# LaserSupply.net
KiCad netlist of a schematic drawn in EAGLE
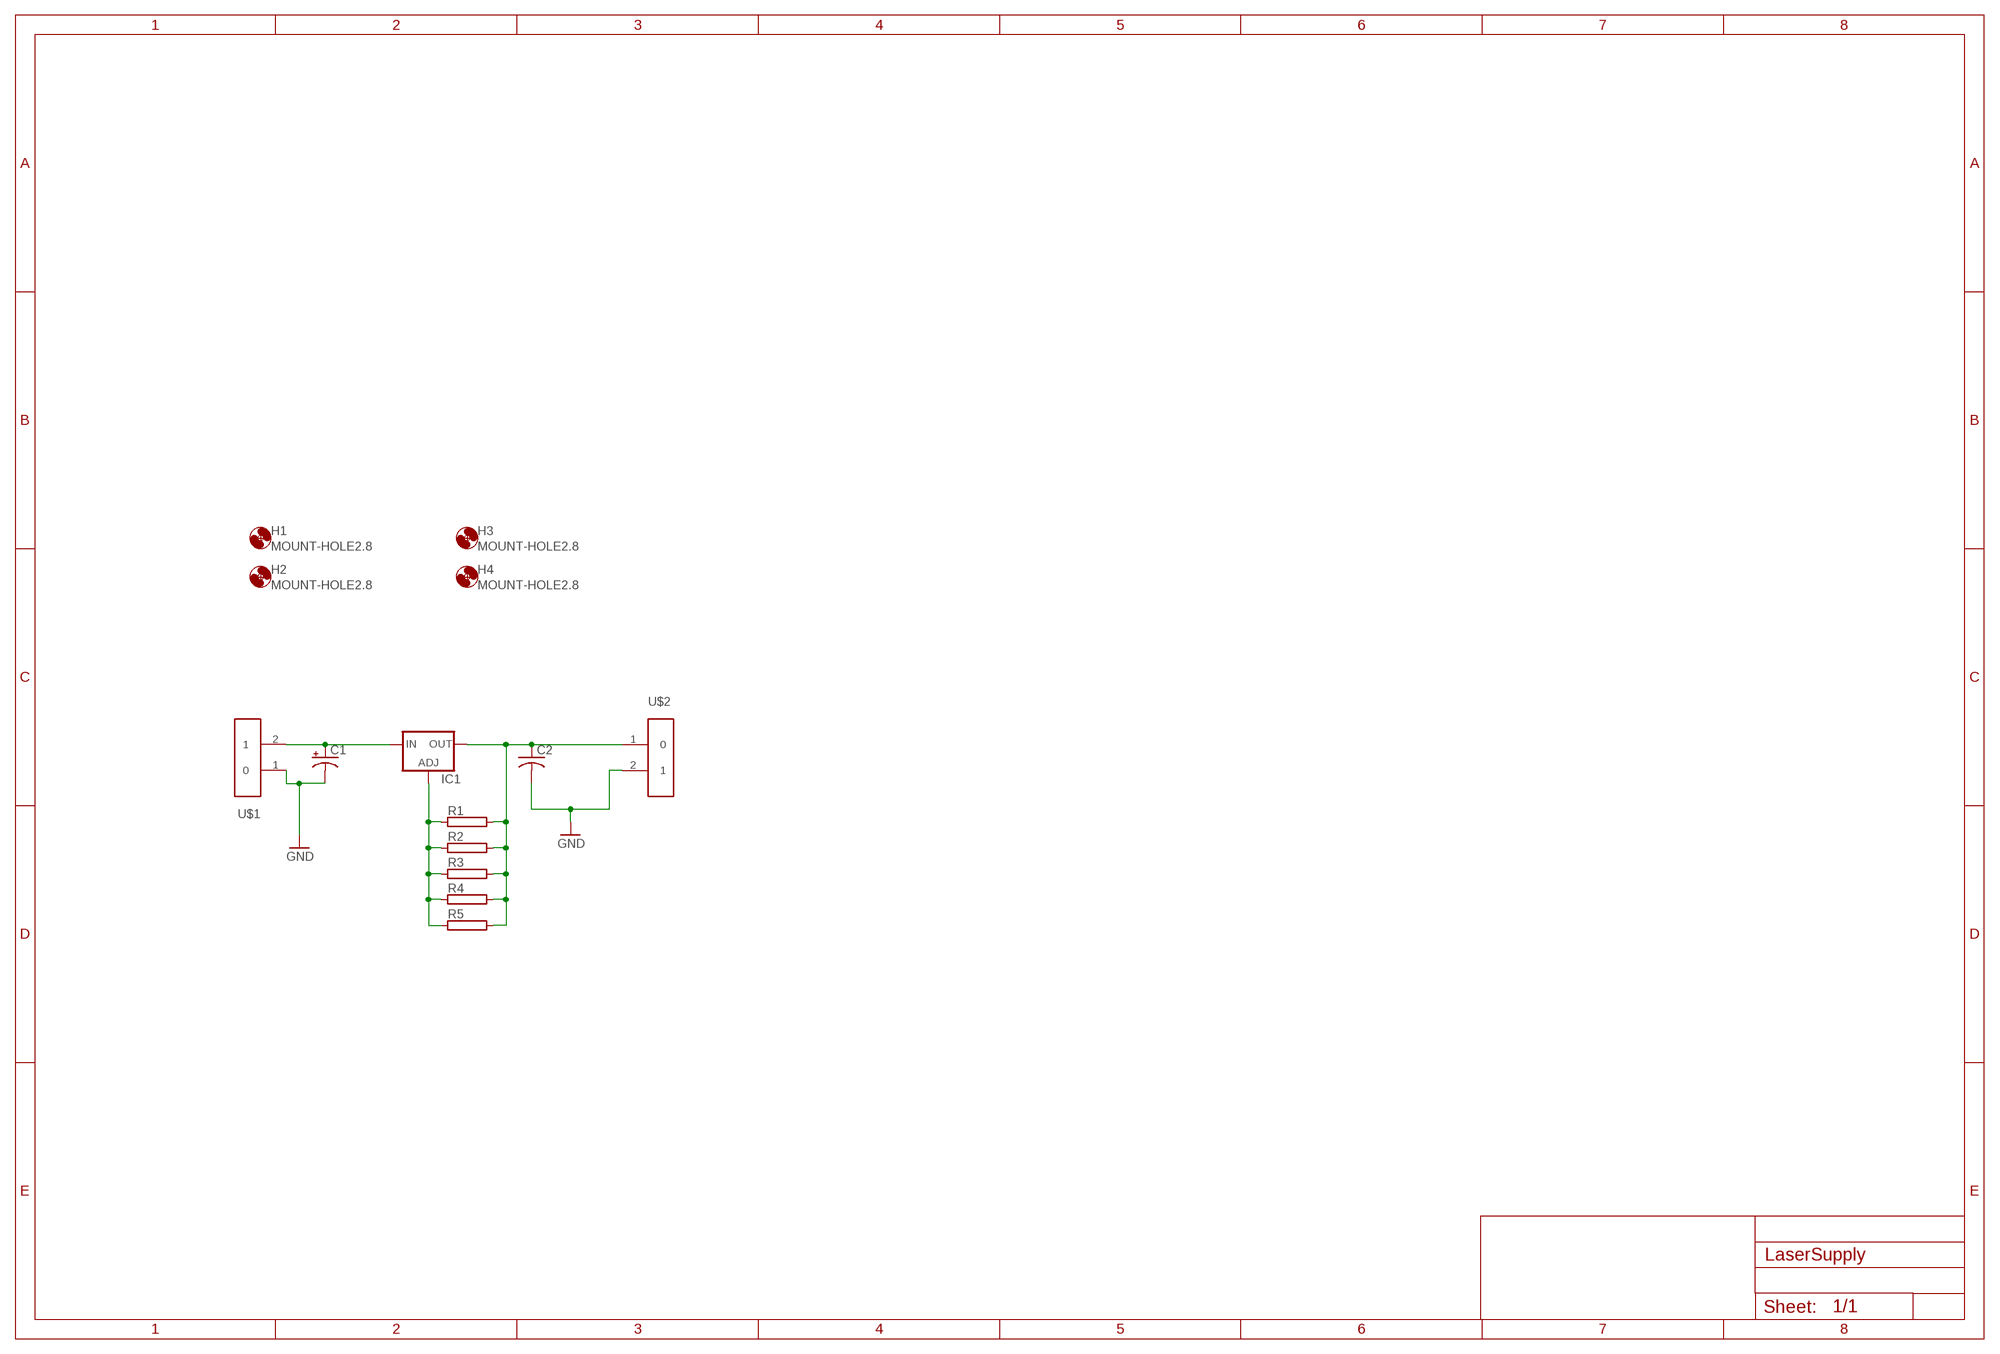
[diagram p0: schematic, sheet 1]

(export (version "E")
  (design (tool "Eeschema 10.0.6"))
  (components
    (comp (ref "C1")
      (value "CPOL-USE2.5-5")
      (footprint "eagle-import:E2,5-5")
      (libsource (lib "eagle-import") (part "CPOL-USE2.5-5"))
    )
    (comp (ref "C2")
      (value "C-US050-024X044")
      (footprint "eagle-import:C050-024X044")
      (libsource (lib "eagle-import") (part "C-US050-024X044"))
    )
    (comp (ref "H1")
      (value "MOUNT-HOLE2.8")
      (footprint "eagle-import:2,8")
      (libsource (lib "eagle-import") (part "MOUNT-HOLE2.8"))
    )
    (comp (ref "H2")
      (value "MOUNT-HOLE2.8")
      (footprint "eagle-import:2,8")
      (libsource (lib "eagle-import") (part "MOUNT-HOLE2.8"))
    )
    (comp (ref "H3")
      (value "MOUNT-HOLE2.8")
      (footprint "eagle-import:2,8")
      (libsource (lib "eagle-import") (part "MOUNT-HOLE2.8"))
    )
    (comp (ref "H4")
      (value "MOUNT-HOLE2.8")
      (footprint "eagle-import:2,8")
      (libsource (lib "eagle-import") (part "MOUNT-HOLE2.8"))
    )
    (comp (ref "IC1")
      (value "LM317TS")
      (footprint "eagle-import:317TS")
      (libsource (lib "eagle-import") (part "LM317TS"))
    )
    (comp (ref "R1")
      (value "RRS1/4")
      (footprint "eagle-import:RS1_4")
      (fields (field (name "MF") "OHMITE") (field (name "MPN") "RRS1K0"))
      (libsource (lib "eagle-import") (part "RRS1/4"))
    )
    (comp (ref "R2")
      (value "RRS1/4")
      (footprint "eagle-import:RS1_4")
      (fields (field (name "MF") "OHMITE") (field (name "MPN") "RRS1K0"))
      (libsource (lib "eagle-import") (part "RRS1/4"))
    )
    (comp (ref "R3")
      (value "RRS1/4")
      (footprint "eagle-import:RS1_4")
      (fields (field (name "MF") "OHMITE") (field (name "MPN") "RRS1K0"))
      (libsource (lib "eagle-import") (part "RRS1/4"))
    )
    (comp (ref "R4")
      (value "RRS1/4")
      (footprint "eagle-import:RS1_4")
      (fields (field (name "MF") "OHMITE") (field (name "MPN") "RRS1K0"))
      (libsource (lib "eagle-import") (part "RRS1/4"))
    )
    (comp (ref "R5")
      (value "RRS1/4")
      (footprint "eagle-import:RS1_4")
      (fields (field (name "MF") "OHMITE") (field (name "MPN") "RRS1K0"))
      (libsource (lib "eagle-import") (part "RRS1/4"))
    )
    (comp (ref "U$1")
      (value "ED2609")
      (footprint "eagle-import:ED2609")
      (libsource (lib "eagle-import") (part "ED2609"))
    )
    (comp (ref "U$2")
      (value "ED2609")
      (footprint "eagle-import:ED2609")
      (libsource (lib "eagle-import") (part "ED2609"))
    )
  )
  (nets
    (net (code "1") (name "GND") (class "Default")
      (node (ref "C1") (pin "-") (pinfunction "-_-") (pintype "passive"))
      (node (ref "C2") (pin "2") (pinfunction "2_2") (pintype "passive"))
      (node (ref "U$1") (pin "1") (pinfunction "0_1") (pintype "bidirectional"))
      (node (ref "U$2") (pin "2") (pinfunction "1_2") (pintype "bidirectional"))
    )
    (net (code "2") (name "Net-(IC1-ADJ)") (class "Default")
      (node (ref "IC1") (pin "1") (pinfunction "ADJ_1") (pintype "input"))
      (node (ref "R1") (pin "1") (pinfunction "1_1") (pintype "passive"))
      (node (ref "R2") (pin "1") (pinfunction "1_1") (pintype "passive"))
      (node (ref "R3") (pin "1") (pinfunction "1_1") (pintype "passive"))
      (node (ref "R4") (pin "1") (pinfunction "1_1") (pintype "passive"))
      (node (ref "R5") (pin "1") (pinfunction "1_1") (pintype "passive"))
    )
    (net (code "3") (name "Net-(IC1-IN)") (class "Default")
      (node (ref "C1") (pin "+") (pinfunction "+_+") (pintype "passive"))
      (node (ref "IC1") (pin "3") (pinfunction "IN_3") (pintype "input"))
      (node (ref "U$1") (pin "2") (pinfunction "1_2") (pintype "bidirectional"))
    )
    (net (code "4") (name "Net-(IC1-OUT)") (class "Default")
      (node (ref "C2") (pin "1") (pinfunction "1_1") (pintype "passive"))
      (node (ref "IC1") (pin "2") (pinfunction "OUT_2") (pintype "passive"))
      (node (ref "R1") (pin "2") (pinfunction "2_2") (pintype "passive"))
      (node (ref "R2") (pin "2") (pinfunction "2_2") (pintype "passive"))
      (node (ref "R3") (pin "2") (pinfunction "2_2") (pintype "passive"))
      (node (ref "R4") (pin "2") (pinfunction "2_2") (pintype "passive"))
      (node (ref "R5") (pin "2") (pinfunction "2_2") (pintype "passive"))
      (node (ref "U$2") (pin "1") (pinfunction "0_1") (pintype "bidirectional"))
    )
  )
)
